# MHR15-inverter_current_sensors-v1.net
KiCad netlist of a schematic drawn in EAGLE
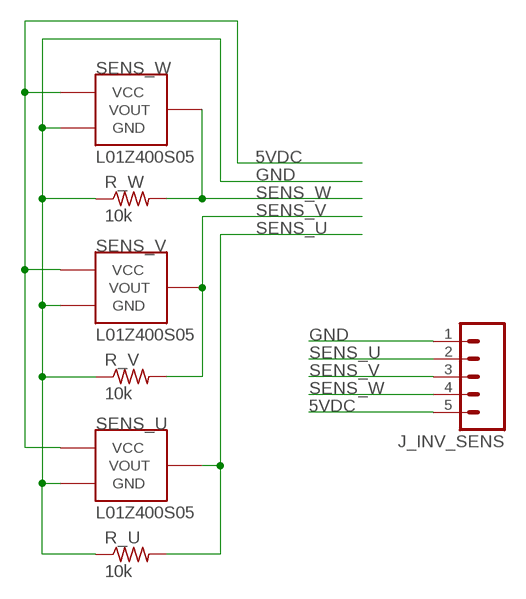
[diagram p0: schematic, sheet 1]

(export (version "E")
  (design (tool "Eeschema 10.0.6"))
  (components
    (comp (ref "J_INV_SENS")
      (value "M05LOCK")
      (footprint "eagle-import:1X05_LOCK")
      (libsource (lib "eagle-import") (part "M05LOCK"))
    )
    (comp (ref "R_U")
      (value "10k")
      (footprint "eagle-import:R0603")
      (libsource (lib "eagle-import") (part "R-US_R0603"))
    )
    (comp (ref "R_V")
      (value "10k")
      (footprint "eagle-import:R0603")
      (libsource (lib "eagle-import") (part "R-US_R0603"))
    )
    (comp (ref "R_W")
      (value "10k")
      (footprint "eagle-import:R0603")
      (libsource (lib "eagle-import") (part "R-US_R0603"))
    )
    (comp (ref "SENS_U")
      (value "L01Z400S05")
      (footprint "eagle-import:L01Z400S05")
      (fields (field (name "MANUFACTURER") "Tamura"))
      (libsource (lib "eagle-import") (part "L01Z400S05"))
    )
    (comp (ref "SENS_V")
      (value "L01Z400S05")
      (footprint "eagle-import:L01Z400S05")
      (fields (field (name "MANUFACTURER") "Tamura"))
      (libsource (lib "eagle-import") (part "L01Z400S05"))
    )
    (comp (ref "SENS_W")
      (value "L01Z400S05")
      (footprint "eagle-import:L01Z400S05")
      (fields (field (name "MANUFACTURER") "Tamura"))
      (libsource (lib "eagle-import") (part "L01Z400S05"))
    )
  )
  (nets
    (net (code "1") (name "/5VDC") (class "Default")
      (node (ref "J_INV_SENS") (pin "5") (pinfunction "5_5") (pintype "passive"))
      (node (ref "SENS_U") (pin "VCC") (pinfunction "VCC_VCC") (pintype "bidirectional"))
      (node (ref "SENS_V") (pin "VCC") (pinfunction "VCC_VCC") (pintype "bidirectional"))
      (node (ref "SENS_W") (pin "VCC") (pinfunction "VCC_VCC") (pintype "bidirectional"))
    )
    (net (code "2") (name "/GND") (class "Default")
      (node (ref "J_INV_SENS") (pin "1") (pinfunction "1_1") (pintype "passive"))
      (node (ref "R_U") (pin "1") (pinfunction "1_1") (pintype "passive"))
      (node (ref "R_V") (pin "1") (pinfunction "1_1") (pintype "passive"))
      (node (ref "R_W") (pin "1") (pinfunction "1_1") (pintype "passive"))
      (node (ref "SENS_U") (pin "GND") (pinfunction "GND_GND") (pintype "bidirectional"))
      (node (ref "SENS_V") (pin "GND") (pinfunction "GND_GND") (pintype "bidirectional"))
      (node (ref "SENS_W") (pin "GND") (pinfunction "GND_GND") (pintype "bidirectional"))
    )
    (net (code "3") (name "/SENS_U") (class "Default")
      (node (ref "J_INV_SENS") (pin "2") (pinfunction "2_2") (pintype "passive"))
      (node (ref "R_U") (pin "2") (pinfunction "2_2") (pintype "passive"))
      (node (ref "SENS_U") (pin "VOUT") (pinfunction "VOUT_VOUT") (pintype "bidirectional"))
    )
    (net (code "4") (name "/SENS_V") (class "Default")
      (node (ref "J_INV_SENS") (pin "3") (pinfunction "3_3") (pintype "passive"))
      (node (ref "R_V") (pin "2") (pinfunction "2_2") (pintype "passive"))
      (node (ref "SENS_V") (pin "VOUT") (pinfunction "VOUT_VOUT") (pintype "bidirectional"))
    )
    (net (code "5") (name "/SENS_W") (class "Default")
      (node (ref "J_INV_SENS") (pin "4") (pinfunction "4_4") (pintype "passive"))
      (node (ref "R_W") (pin "2") (pinfunction "2_2") (pintype "passive"))
      (node (ref "SENS_W") (pin "VOUT") (pinfunction "VOUT_VOUT") (pintype "bidirectional"))
    )
  )
)
